# schematic.net
KiCad netlist of a schematic drawn in EasyEDA
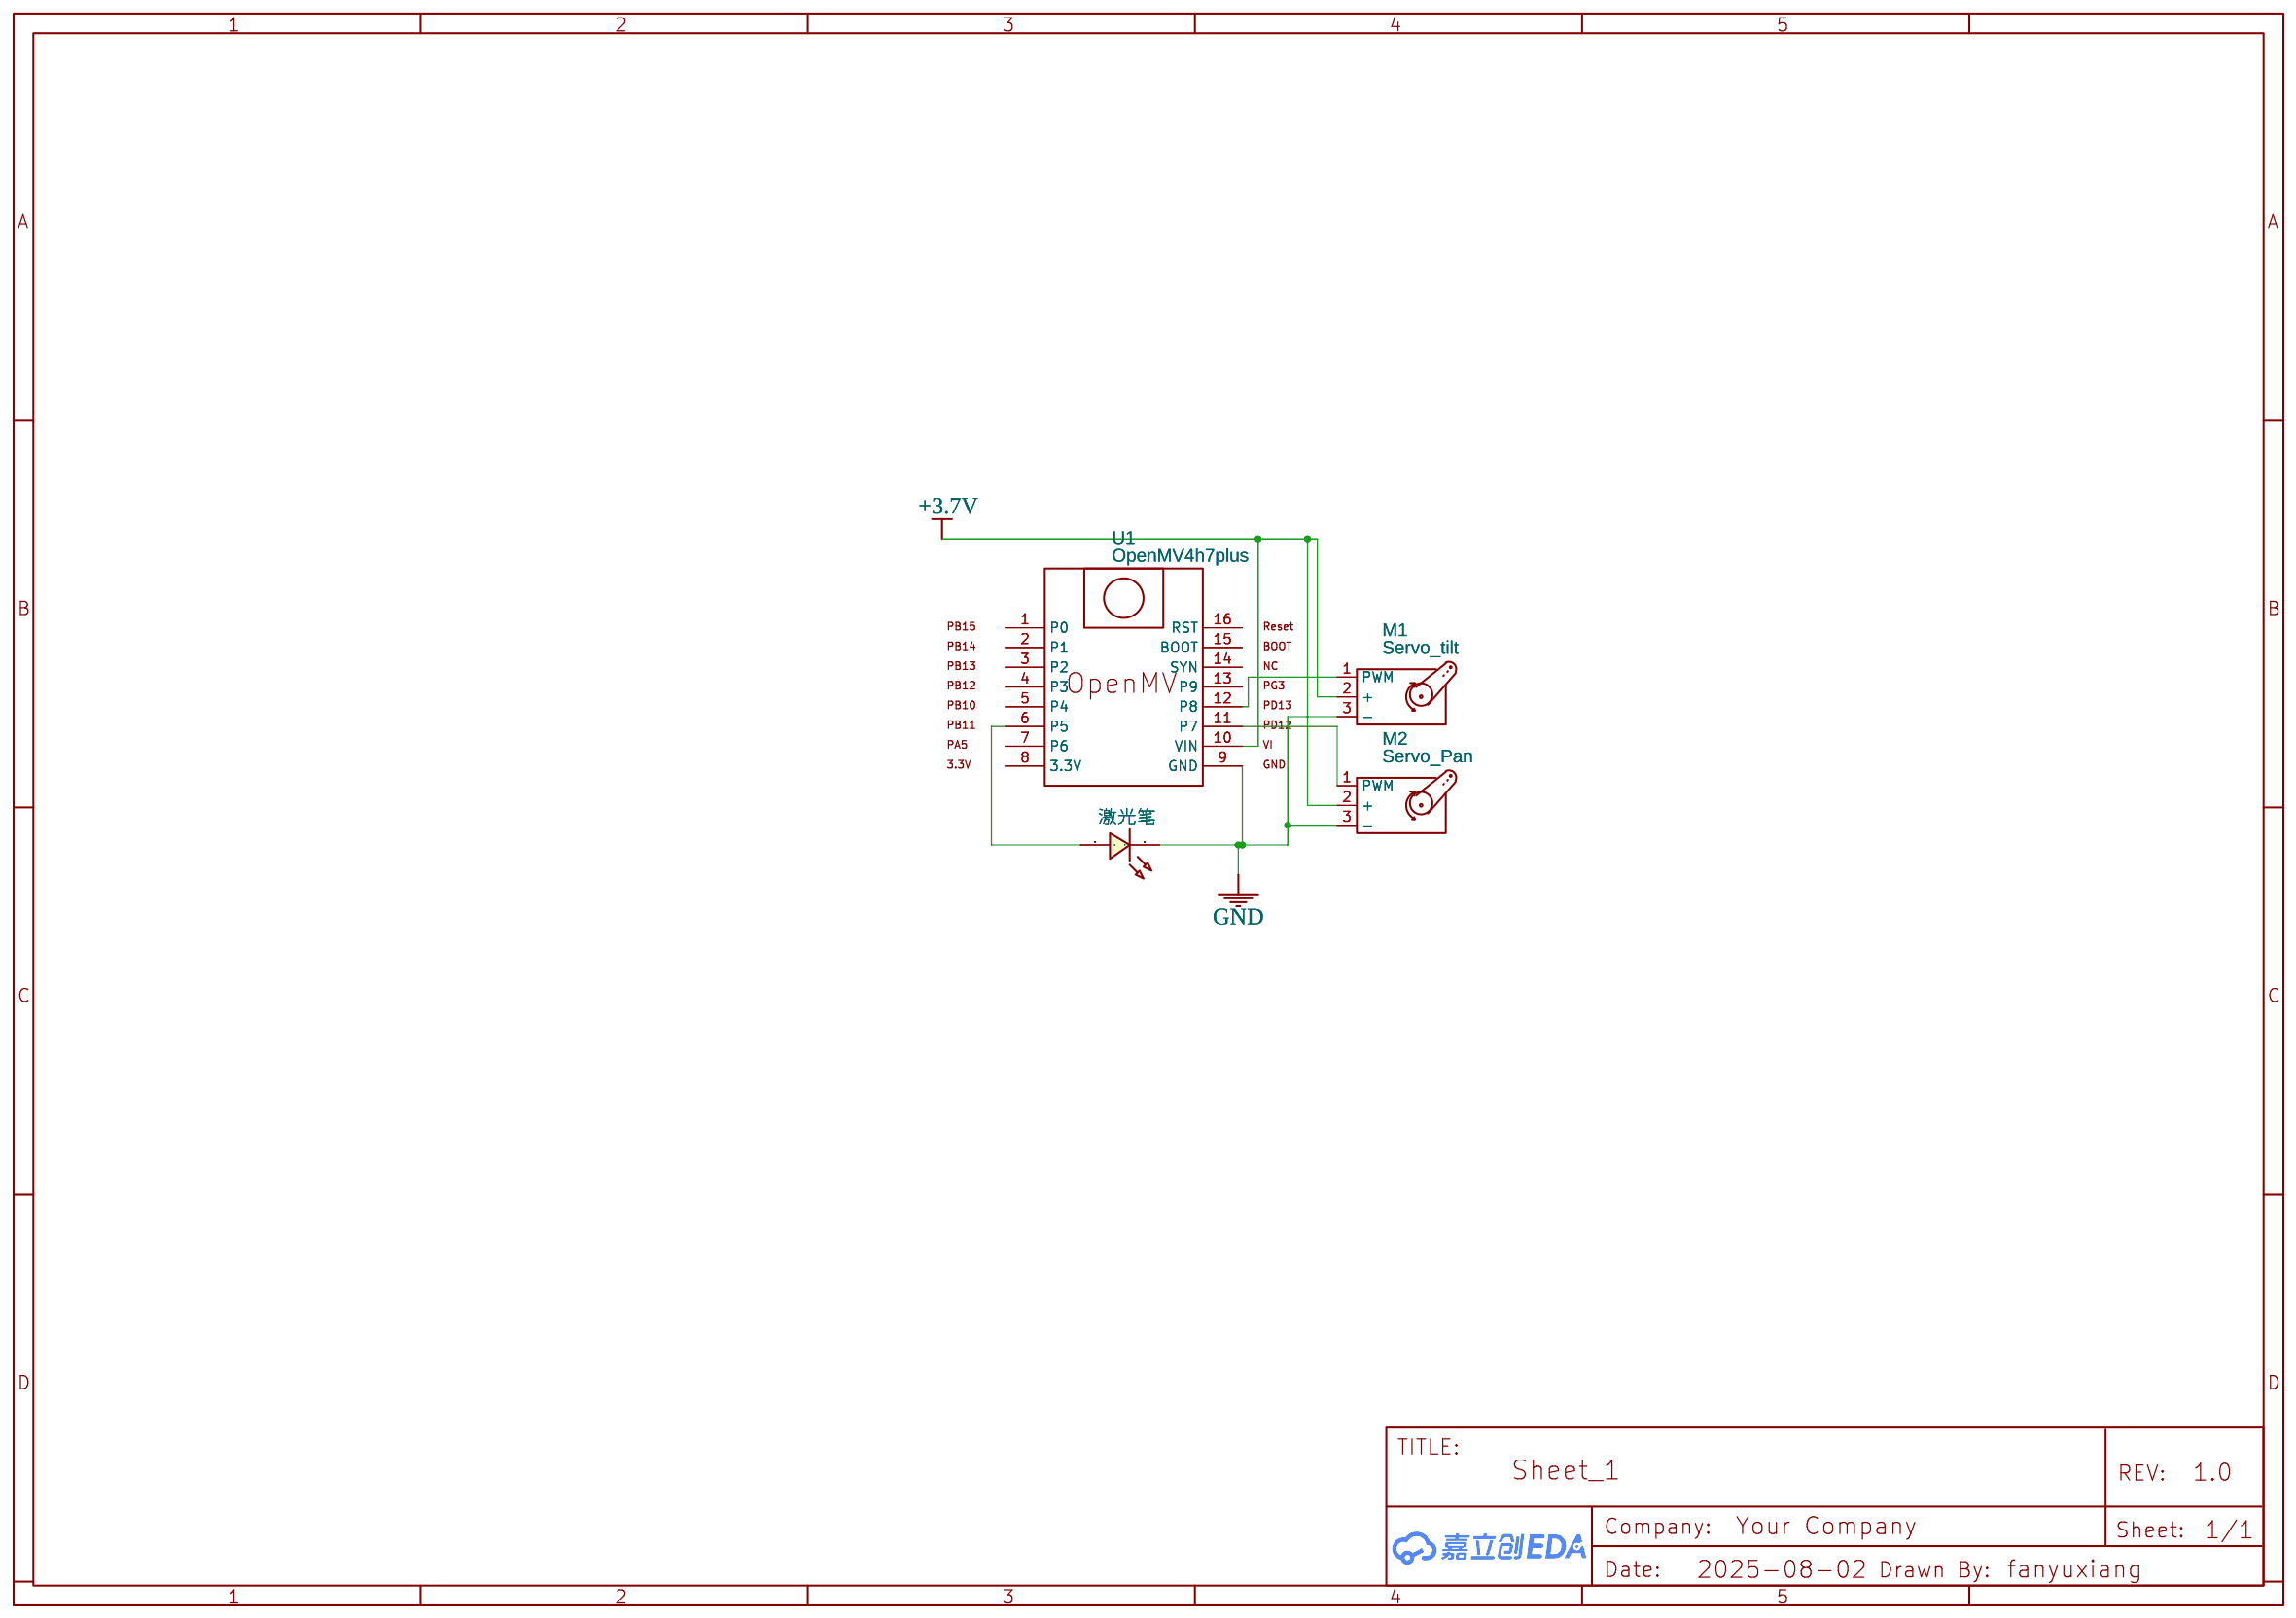
[diagram p0: Sheet_1]
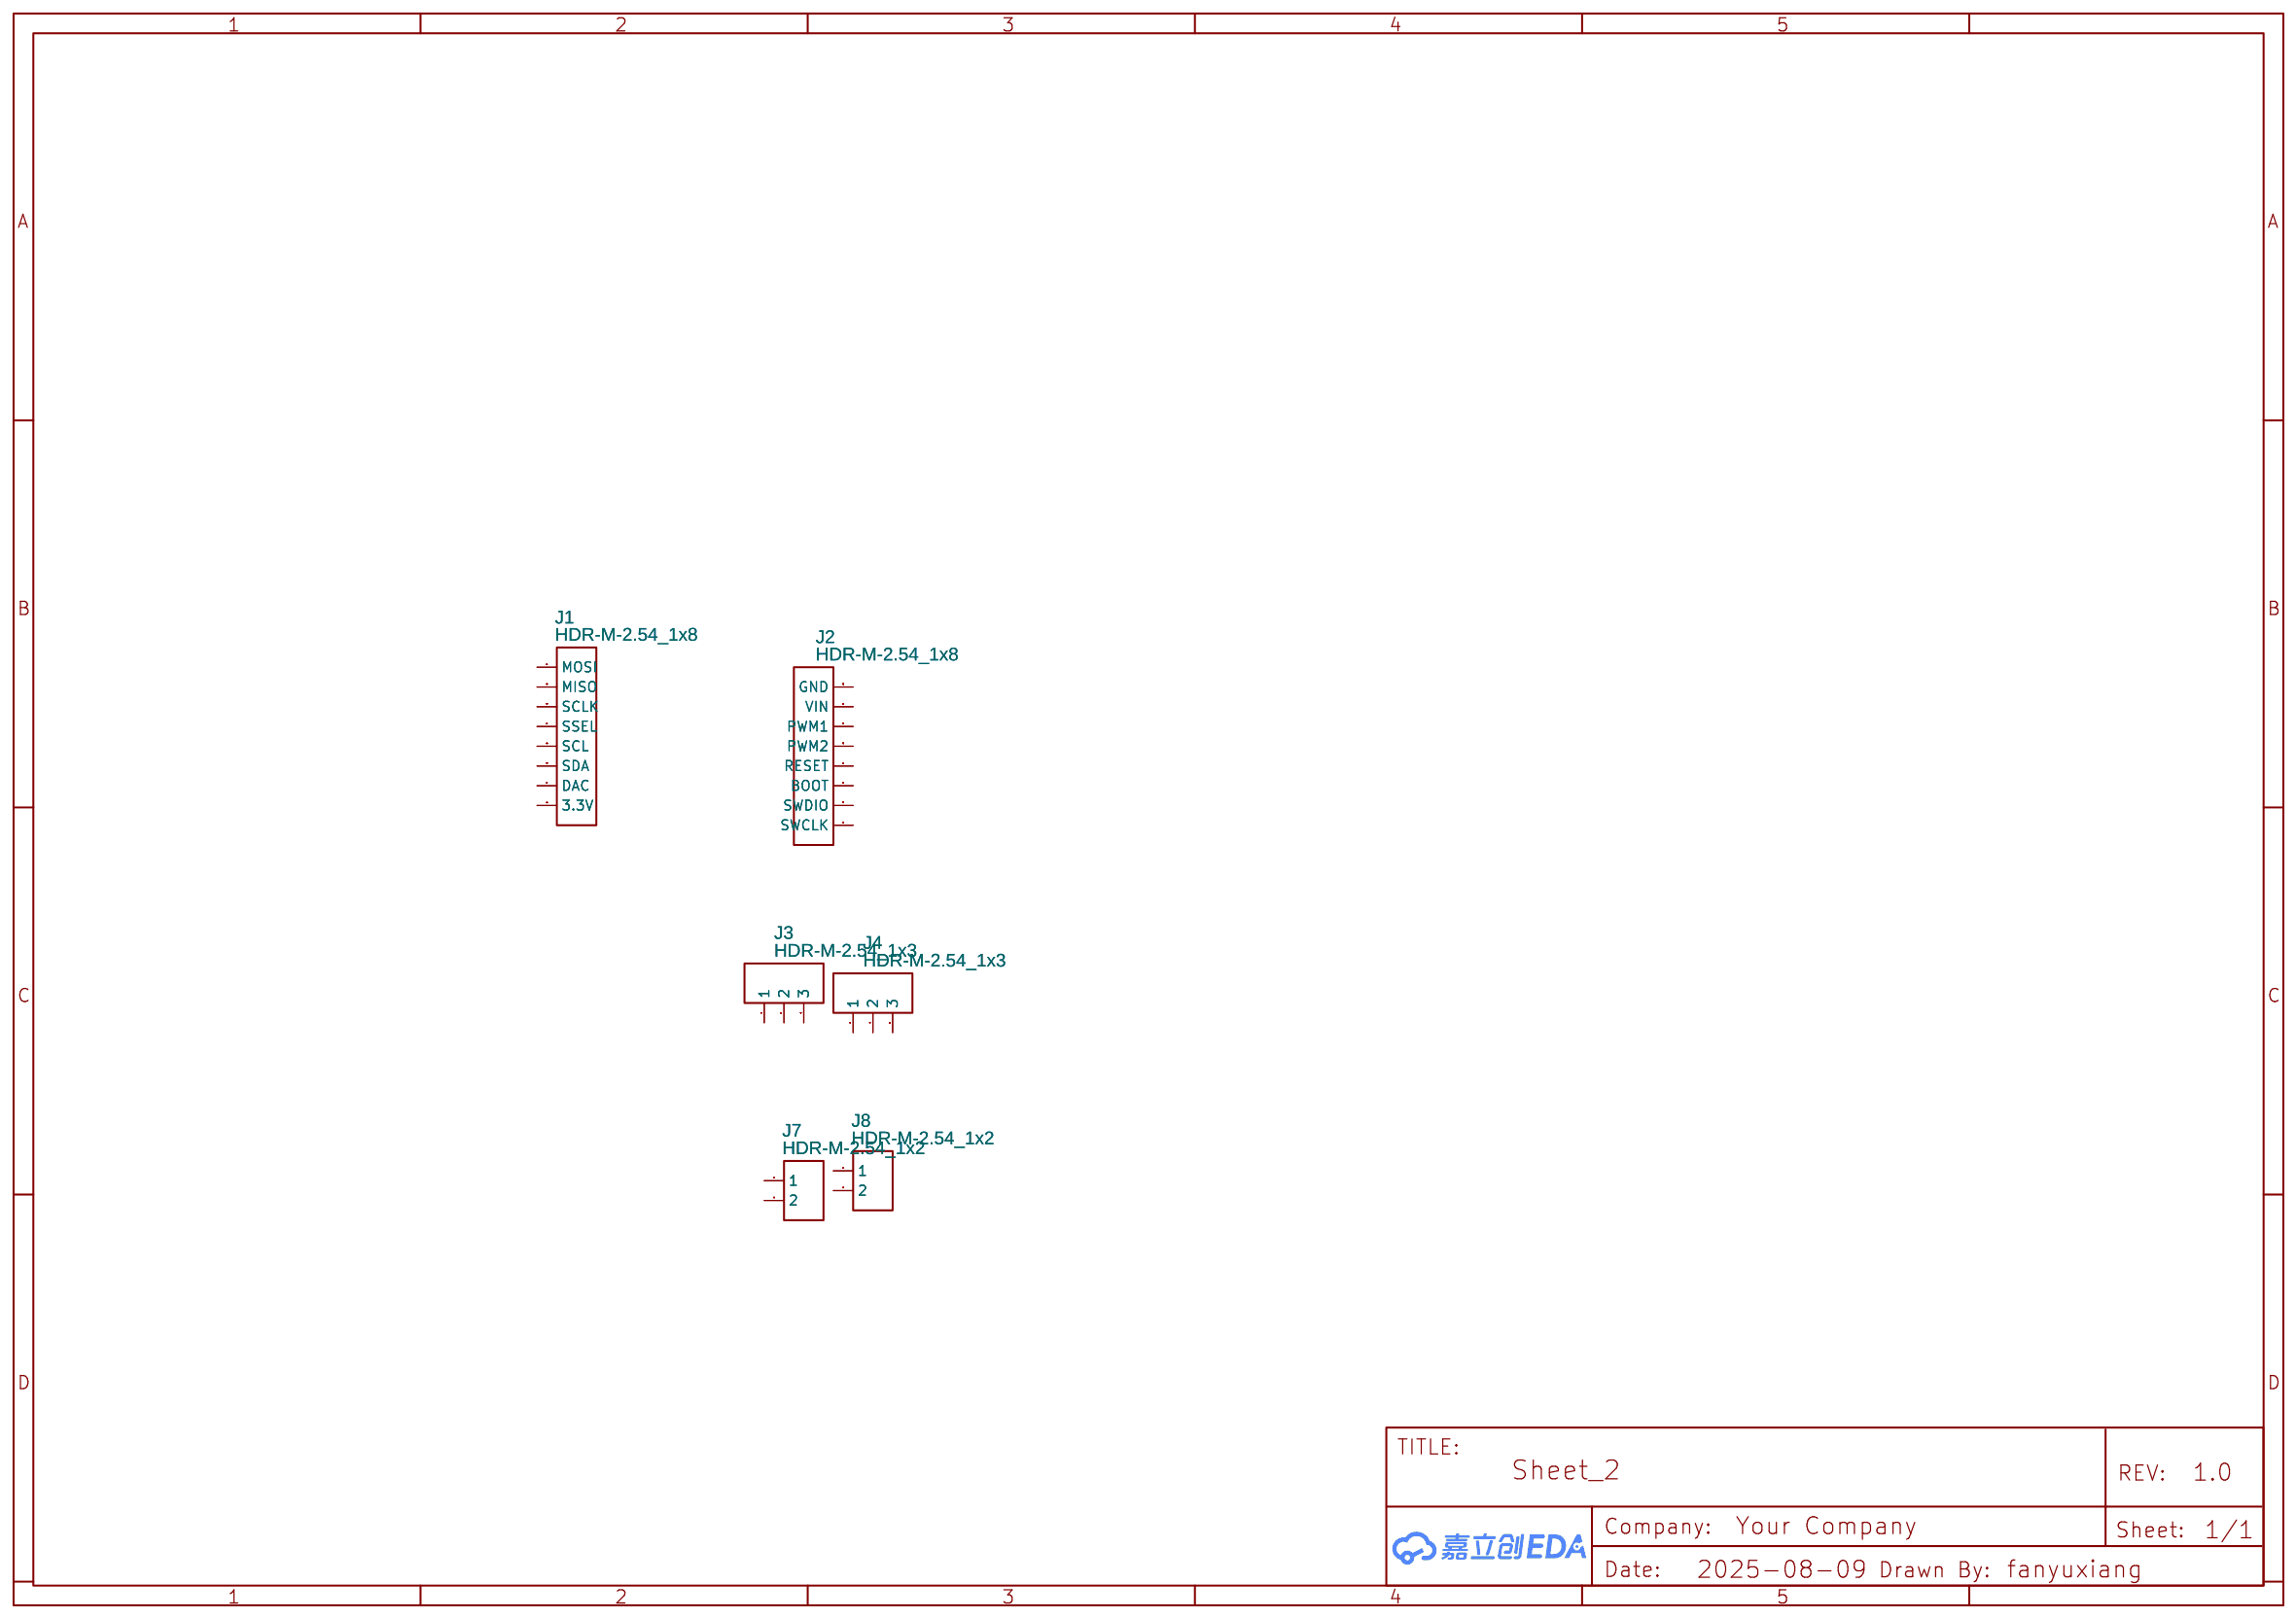
[diagram p1: Sheet_2]

(export (version "E")
  (design (tool "Eeschema 10.0.6"))
  (components
    (comp (ref "LASER")
      (value "激光笔")
      (fields
        (field (name "Manufacturer Part") "LASERDI SPL-PL90 A")
        (field (name "Manufacturer") "Infineon(英飞凌)")
      )
      (libsource (lib "") (part "LASERDI SPL-PL90 A"))
    )
    (comp (ref "M1") (value "Servo_tilt") (libsource (lib "") (part "Motor_Servo")))
    (comp (ref "M2") (value "Servo_Pan") (libsource (lib "") (part "Motor_Servo")))
    (comp (ref "U1") (value "OpenMV4h7plus") (libsource (lib "") (part "OpenMV4h7plus")))
    (comp (ref "J1") (value "HDR-M-2.54_1x8") (libsource (lib "") (part "HDR-M-2.54_1x8")))
    (comp (ref "J2") (value "HDR-M-2.54_1x8") (libsource (lib "") (part "HDR-M-2.54_1x8_1")))
    (comp (ref "J3") (value "HDR-M-2.54_1x3") (libsource (lib "") (part "HDR-M-2.54_1x3")))
    (comp (ref "J4") (value "HDR-M-2.54_1x3") (libsource (lib "") (part "HDR-M-2.54_1x3")))
    (comp (ref "J7") (value "HDR-M-2.54_1x2") (libsource (lib "") (part "HDR-M-2.54_1x2")))
    (comp (ref "J8") (value "HDR-M-2.54_1x2") (libsource (lib "") (part "HDR-M-2.54_1x2")))
  )
  (nets
    (net (code "1") (name "+3.7V") (class "Default")
      (node (ref "M1") (pin "2") (pinfunction "+_2") (pintype "unspecified"))
      (node (ref "M2") (pin "2") (pinfunction "+_2") (pintype "unspecified"))
      (node (ref "U1") (pin "10") (pinfunction "VIN_10") (pintype "unspecified"))
    )
    (net (code "2") (name "GND") (class "Default")
      (node (ref "LASER") (pin "1") (pinfunction "-_1") (pintype "unspecified"))
      (node (ref "M1") (pin "3") (pinfunction "-_3") (pintype "unspecified"))
      (node (ref "M2") (pin "3") (pinfunction "-_3") (pintype "unspecified"))
      (node (ref "U1") (pin "9") (pinfunction "GND_9") (pintype "unspecified"))
    )
    (net (code "3") (name "Net-(LASER-+)") (class "Default")
      (node (ref "LASER") (pin "2") (pinfunction "+_2") (pintype "unspecified"))
      (node (ref "U1") (pin "6") (pinfunction "P5_6") (pintype "unspecified"))
    )
    (net (code "4") (name "Net-(M1-PWM)") (class "Default")
      (node (ref "M1") (pin "1") (pinfunction "PWM_1") (pintype "unspecified"))
      (node (ref "U1") (pin "12") (pinfunction "P8_12") (pintype "unspecified"))
    )
    (net (code "5") (name "Net-(M2-PWM)") (class "Default")
      (node (ref "M2") (pin "1") (pinfunction "PWM_1") (pintype "unspecified"))
      (node (ref "U1") (pin "11") (pinfunction "P7_11") (pintype "unspecified"))
    )
    (net (code "6") (name "unconnected-(J1-3.3V-Pad18)") (class "Default")
      (node (ref "J1") (pin "18") (pinfunction "3.3V_18") (pintype "unspecified"))
    )
    (net (code "7") (name "unconnected-(J1-DAC-Pad17)") (class "Default")
      (node (ref "J1") (pin "17") (pinfunction "DAC_17") (pintype "unspecified"))
    )
    (net (code "8") (name "unconnected-(J1-MISO-Pad12)") (class "Default")
      (node (ref "J1") (pin "12") (pinfunction "MISO_12") (pintype "unspecified"))
    )
    (net (code "9") (name "unconnected-(J1-MOSI-Pad11)") (class "Default")
      (node (ref "J1") (pin "11") (pinfunction "MOSI_11") (pintype "unspecified"))
    )
    (net (code "10") (name "unconnected-(J1-SCL-Pad15)") (class "Default")
      (node (ref "J1") (pin "15") (pinfunction "SCL_15") (pintype "unspecified"))
    )
    (net (code "11") (name "unconnected-(J1-SCLK-Pad13)") (class "Default")
      (node (ref "J1") (pin "13") (pinfunction "SCLK_13") (pintype "unspecified"))
    )
    (net (code "12") (name "unconnected-(J1-SDA-Pad16)") (class "Default")
      (node (ref "J1") (pin "16") (pinfunction "SDA_16") (pintype "unspecified"))
    )
    (net (code "13") (name "unconnected-(J1-SSEL-Pad14)") (class "Default")
      (node (ref "J1") (pin "14") (pinfunction "SSEL_14") (pintype "unspecified"))
    )
    (net (code "14") (name "unconnected-(J2-BOOT-Pad23)") (class "Default")
      (node (ref "J2") (pin "23") (pinfunction "BOOT_23") (pintype "unspecified"))
    )
    (net (code "15") (name "unconnected-(J2-GND-Pad28)") (class "Default")
      (node (ref "J2") (pin "28") (pinfunction "GND_28") (pintype "unspecified"))
    )
    (net (code "16") (name "unconnected-(J2-PWM1-Pad26)") (class "Default")
      (node (ref "J2") (pin "26") (pinfunction "PWM1_26") (pintype "unspecified"))
    )
    (net (code "17") (name "unconnected-(J2-PWM2-Pad25)") (class "Default")
      (node (ref "J2") (pin "25") (pinfunction "PWM2_25") (pintype "unspecified"))
    )
    (net (code "18") (name "unconnected-(J2-RESET-Pad24)") (class "Default")
      (node (ref "J2") (pin "24") (pinfunction "RESET_24") (pintype "unspecified"))
    )
    (net (code "19") (name "unconnected-(J2-SWCLK-Pad21)") (class "Default")
      (node (ref "J2") (pin "21") (pinfunction "SWCLK_21") (pintype "unspecified"))
    )
    (net (code "20") (name "unconnected-(J2-SWDIO-Pad22)") (class "Default")
      (node (ref "J2") (pin "22") (pinfunction "SWDIO_22") (pintype "unspecified"))
    )
    (net (code "21") (name "unconnected-(J2-VIN-Pad27)") (class "Default")
      (node (ref "J2") (pin "27") (pinfunction "VIN_27") (pintype "unspecified"))
    )
    (net (code "22") (name "unconnected-(J3-Pad1)") (class "Default")
      (node (ref "J3") (pin "1") (pinfunction "1_1") (pintype "input"))
    )
    (net (code "23") (name "unconnected-(J3-Pad2)") (class "Default")
      (node (ref "J3") (pin "2") (pinfunction "2_2") (pintype "input"))
    )
    (net (code "24") (name "unconnected-(J3-Pad3)") (class "Default")
      (node (ref "J3") (pin "3") (pinfunction "3_3") (pintype "input"))
    )
    (net (code "25") (name "unconnected-(J4-Pad1)") (class "Default")
      (node (ref "J4") (pin "1") (pinfunction "1_1") (pintype "input"))
    )
    (net (code "26") (name "unconnected-(J4-Pad2)") (class "Default")
      (node (ref "J4") (pin "2") (pinfunction "2_2") (pintype "input"))
    )
    (net (code "27") (name "unconnected-(J4-Pad3)") (class "Default")
      (node (ref "J4") (pin "3") (pinfunction "3_3") (pintype "input"))
    )
    (net (code "28") (name "unconnected-(J7-Pad1)") (class "Default")
      (node (ref "J7") (pin "1") (pinfunction "1_1") (pintype "unspecified"))
    )
    (net (code "29") (name "unconnected-(J7-Pad2)") (class "Default")
      (node (ref "J7") (pin "2") (pinfunction "2_2") (pintype "unspecified"))
    )
    (net (code "30") (name "unconnected-(J8-Pad1)") (class "Default")
      (node (ref "J8") (pin "1") (pinfunction "1_1") (pintype "unspecified"))
    )
    (net (code "31") (name "unconnected-(J8-Pad2)") (class "Default")
      (node (ref "J8") (pin "2") (pinfunction "2_2") (pintype "unspecified"))
    )
    (net (code "32") (name "unconnected-(U1-3.3V-Pad8)") (class "Default")
      (node (ref "U1") (pin "8") (pinfunction "3.3V_8") (pintype "unspecified"))
    )
    (net (code "33") (name "unconnected-(U1-BOOT-Pad15)") (class "Default")
      (node (ref "U1") (pin "15") (pinfunction "BOOT_15") (pintype "unspecified"))
    )
    (net (code "34") (name "unconnected-(U1-P0-Pad1)") (class "Default")
      (node (ref "U1") (pin "1") (pinfunction "P0_1") (pintype "unspecified"))
    )
    (net (code "35") (name "unconnected-(U1-P1-Pad2)") (class "Default")
      (node (ref "U1") (pin "2") (pinfunction "P1_2") (pintype "unspecified"))
    )
    (net (code "36") (name "unconnected-(U1-P2-Pad3)") (class "Default")
      (node (ref "U1") (pin "3") (pinfunction "P2_3") (pintype "unspecified"))
    )
    (net (code "37") (name "unconnected-(U1-P3-Pad4)") (class "Default")
      (node (ref "U1") (pin "4") (pinfunction "P3_4") (pintype "unspecified"))
    )
    (net (code "38") (name "unconnected-(U1-P4-Pad5)") (class "Default")
      (node (ref "U1") (pin "5") (pinfunction "P4_5") (pintype "unspecified"))
    )
    (net (code "39") (name "unconnected-(U1-P6-Pad7)") (class "Default")
      (node (ref "U1") (pin "7") (pinfunction "P6_7") (pintype "unspecified"))
    )
    (net (code "40") (name "unconnected-(U1-P9-Pad13)") (class "Default")
      (node (ref "U1") (pin "13") (pinfunction "P9_13") (pintype "unspecified"))
    )
    (net (code "41") (name "unconnected-(U1-RST-Pad16)") (class "Default")
      (node (ref "U1") (pin "16") (pinfunction "RST_16") (pintype "unspecified"))
    )
    (net (code "42") (name "unconnected-(U1-SYN-Pad14)") (class "Default")
      (node (ref "U1") (pin "14") (pinfunction "SYN_14") (pintype "unspecified"))
    )
  )
)
